# Fri3D_2020_Peripherals.net
KiCad netlist of a schematic drawn in Altium Designer
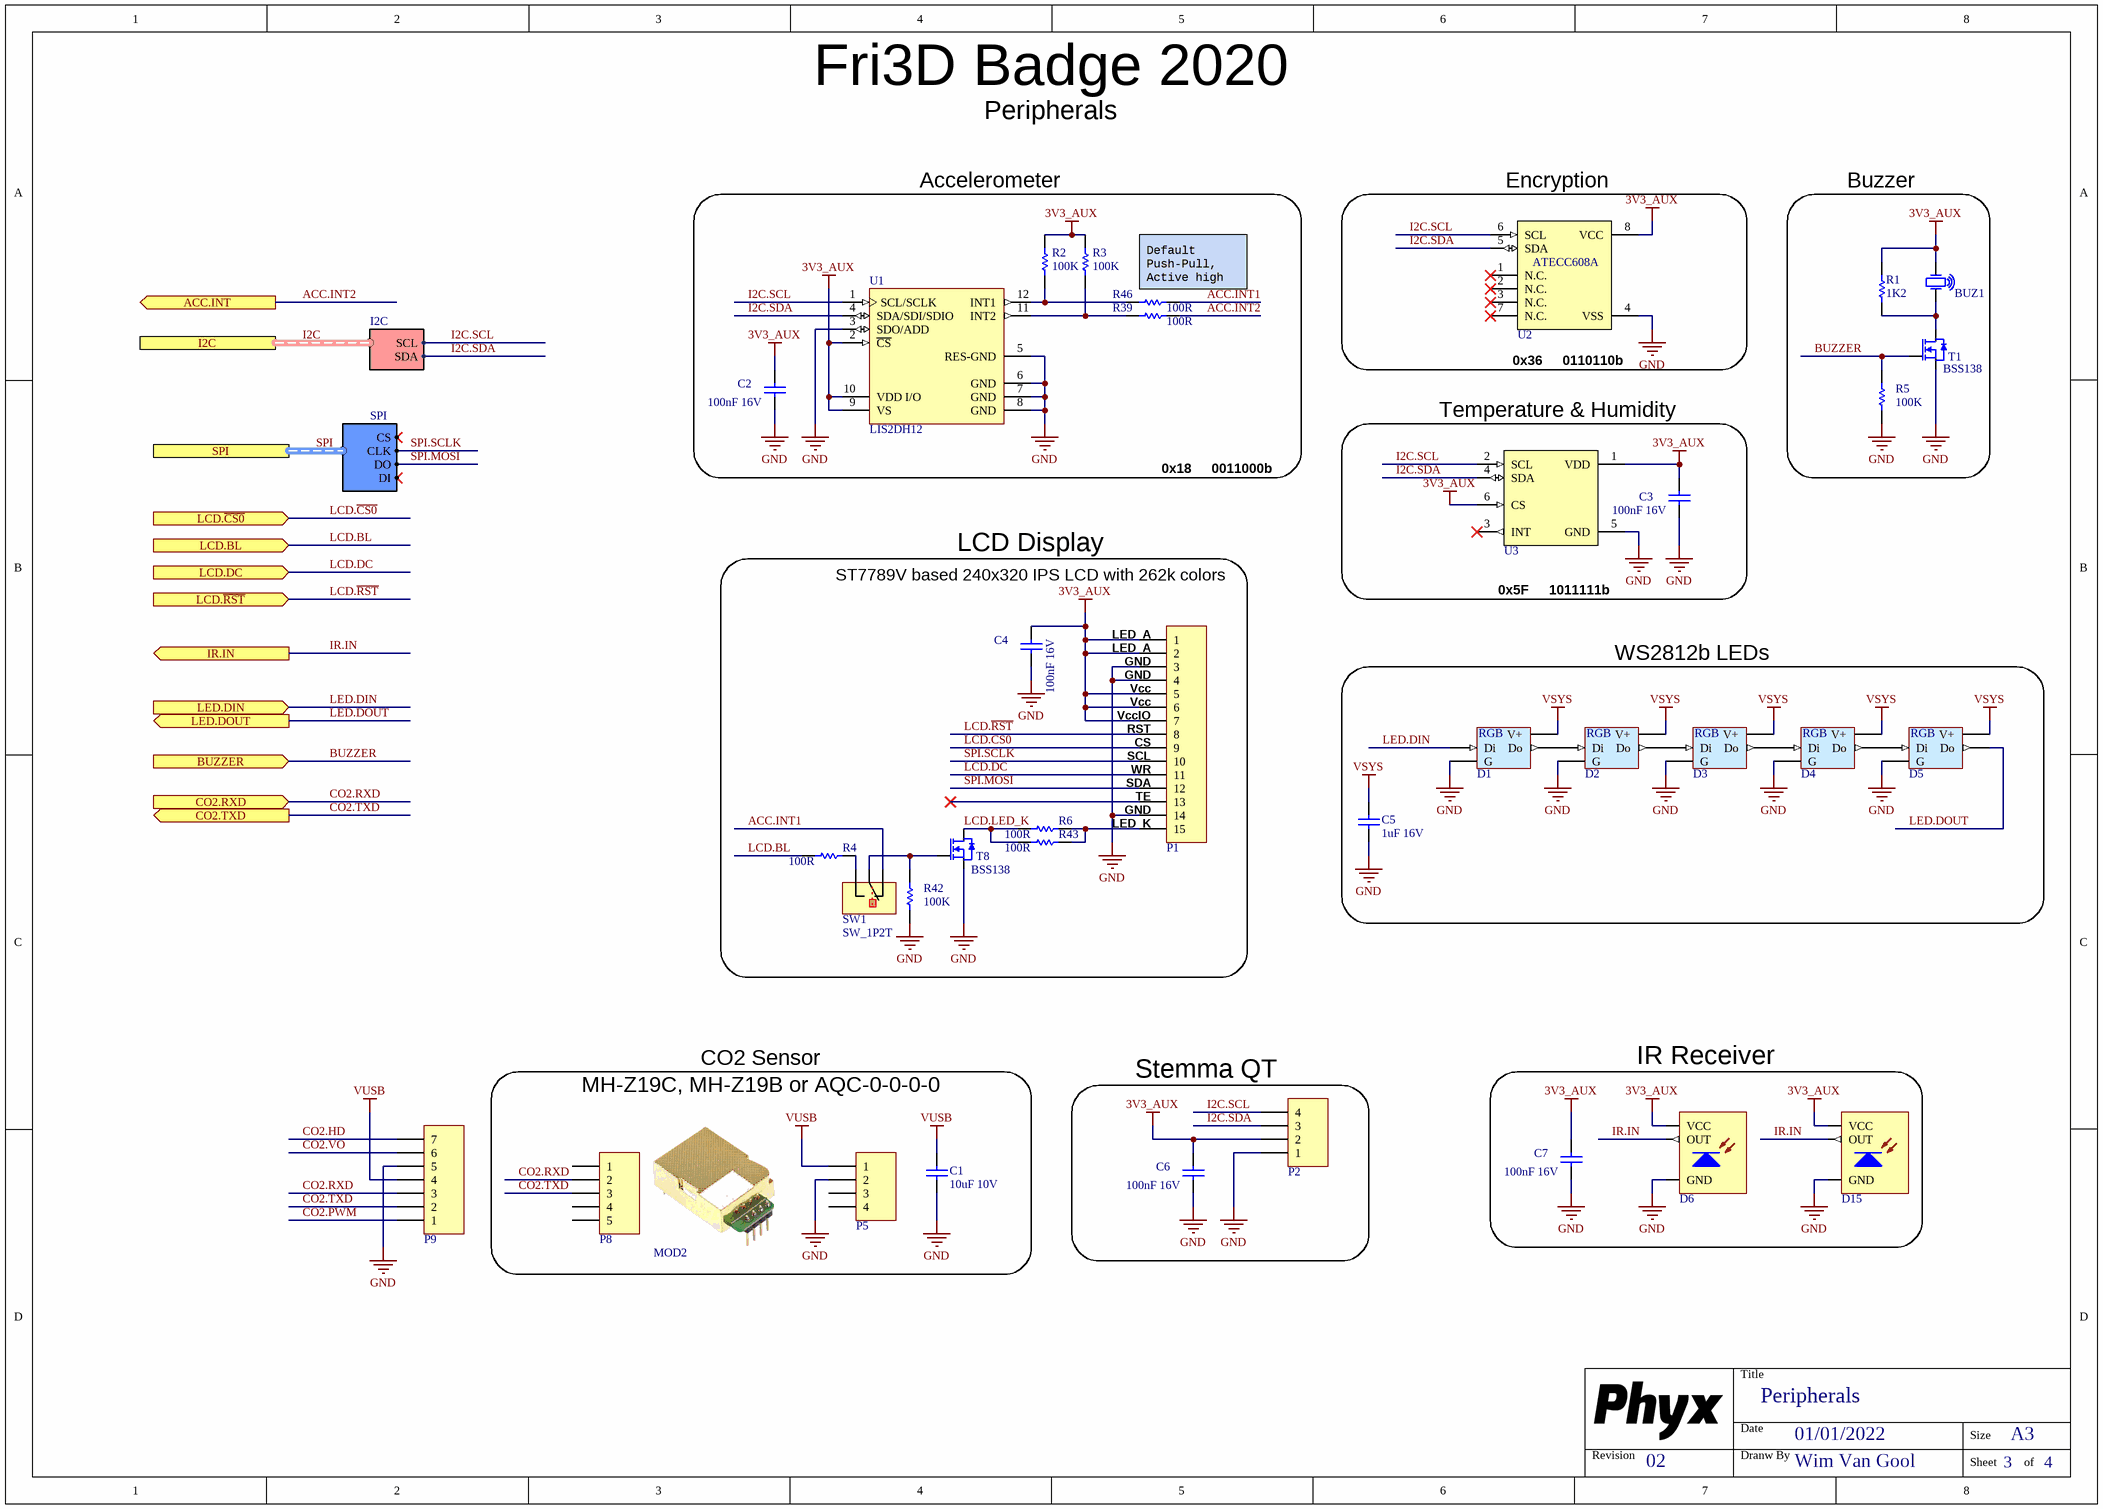
[diagram p0: Fri3D_2020_Peripherals.SchDoc]

(export (version "E")
  (design (tool "Eeschema 10.0.6"))
  (components
    (comp (ref "BUZ1")
      (value "12x12x3mm Piezo Buzzer Transducer 81dB")
      (footprint "CUI_CMT-1203-SMT")
      (description "Crystal Oscillator")
      (libsource (lib "Phyx_Components") (part "Buzzer"))
    )
    (comp (ref "C1")
      (value "10uF 10V")
      (footprint "C0805_N")
      (description "Capacitor Ceramic")
      (fields (field (name "Comment") "CAP_CERAMIC"))
      (libsource (lib "Phyx_Components") (part "CAP_CERAMIC"))
    )
    (comp (ref "C2")
      (value "100nF 16V")
      (footprint "C0603_N")
      (description "Capacitor Ceramic")
      (libsource (lib "Phyx_Components") (part "CAP_CERAMIC"))
    )
    (comp (ref "C3")
      (value "100nF 16V")
      (footprint "C0603_N")
      (description "Capacitor Ceramic")
      (libsource (lib "Phyx_Components") (part "CAP_CERAMIC"))
    )
    (comp (ref "C4")
      (value "100nF 16V")
      (footprint "C0603_N")
      (description "Capacitor Ceramic")
      (libsource (lib "Phyx_Components") (part "CAP_CERAMIC"))
    )
    (comp (ref "C5")
      (value "1uF 16V")
      (footprint "C0603_N")
      (description "Capacitor Ceramic")
      (fields (field (name "Comment") "CAP_CERAMIC"))
      (libsource (lib "Phyx_Components") (part "CAP_CERAMIC"))
    )
    (comp (ref "C6")
      (value "100nF 16V")
      (footprint "C0603_N")
      (description "Capacitor Ceramic")
      (libsource (lib "Phyx_Components") (part "CAP_CERAMIC"))
    )
    (comp (ref "C7")
      (value "100nF 16V")
      (footprint "C0603_N")
      (description "Capacitor Ceramic")
      (libsource (lib "Phyx_Components") (part "CAP_CERAMIC"))
    )
    (comp (ref "D1")
      (value "WS2812 based digital RGB LED 5050 Black package")
      (footprint "LED_5050_WS2812B_BLACK")
      (description "=Description")
      (libsource (lib "Phyx_Components") (part "LED_RGB_WS2812B_5050"))
    )
    (comp (ref "D2")
      (value "WS2812 based digital RGB LED 5050 Black package")
      (footprint "LED_5050_WS2812B_BLACK")
      (description "=Description")
      (libsource (lib "Phyx_Components") (part "LED_RGB_WS2812B_5050"))
    )
    (comp (ref "D3")
      (value "WS2812 based digital RGB LED 5050 Black package")
      (footprint "LED_5050_WS2812B_BLACK")
      (description "=Description")
      (libsource (lib "Phyx_Components") (part "LED_RGB_WS2812B_5050"))
    )
    (comp (ref "D4")
      (value "WS2812 based digital RGB LED 5050 Black package")
      (footprint "LED_5050_WS2812B_BLACK")
      (description "=Description")
      (libsource (lib "Phyx_Components") (part "LED_RGB_WS2812B_5050"))
    )
    (comp (ref "D5")
      (value "WS2812 based digital RGB LED 5050 Black package")
      (footprint "LED_5050_WS2812B_BLACK")
      (description "=Description")
      (libsource (lib "Phyx_Components") (part "LED_RGB_WS2812B_5050"))
    )
    (comp (ref "D6")
      (value "IRM-3638N3F14 Infrared Receiver 38 kHz 45° 2.7-5.5V")
      (footprint "VIS_TSOP381x_BENT")
      (description "=Description")
      (libsource (lib "Phyx_Components") (part "PHO_IR_TSOP381x"))
    )
    (comp (ref "D15")
      (value "ZIRM-5042B-42-Z2 Infrared Receiver 38 kHz 45° 2.7-5.5V 940nm")
      (footprint "CHAU_ZIRM-5042B-42-Z2")
      (description "=Description")
      (libsource (lib "Phyx_Components") (part "PHO_IR_TSOP381x"))
    )
    (comp (ref "MOD2")
      (value "MH-Z19C CO2 Sensor TH Pins")
      (footprint "WIN_MH-Z19x-PH")
      (description "CO2 MH-Z19C-PH")
      (libsource (lib "Phyx_Components") (part "WIN_MH-Z19x-PH"))
    )
    (comp (ref "P1")
      (value "Bottom contact FPC 0.3mm pitch 15 contacts")
      (footprint "FPC_AFE03-S15FMA-1H")
      (libsource (lib "Phyx_Components") (part "Header 15"))
    )
    (comp (ref "P2")
      (value "Header 1.0mm RA Shrouded 4")
      (footprint "WE_665104131822")
      (libsource (lib "Phyx_Components") (part "Header 4"))
    )
    (comp (ref "P5")
      (value "Receptacle 4 SMD Type 2")
      (footprint "WE_61000413321")
      (description "Receptacle # 2.54mm 4way Type 2")
      (libsource (lib "") (part "Header 4_1"))
    )
    (comp (ref "P8")
      (value "Receptacle 5 SMD Type 2")
      (footprint "WE_61000513321")
      (description "Receptacle # 2.54mm 5way Type 2")
      (libsource (lib "Phyx_Components") (part "Header 5"))
    )
    (comp (ref "P9")
      (value "Molex Picoblade SMD RA 532610771")
      (footprint "MLX_53261-0771")
      (description "HDR # RA SHR 1.25mm 7way Molex Picoblade")
      (libsource (lib "Phyx_Components") (part "Header 7"))
    )
    (comp (ref "R1")
      (value "1K2")
      (footprint "R0603_N")
      (fields (field (name "Comment") "RESISTOR"))
      (libsource (lib "Phyx_Components") (part "RESISTOR"))
    )
    (comp (ref "R2")
      (value "100K")
      (footprint "R0603_N")
      (fields (field (name "Comment") "RESISTOR"))
      (libsource (lib "Phyx_Components") (part "RESISTOR"))
    )
    (comp (ref "R3")
      (value "100K")
      (footprint "R0603_N")
      (fields (field (name "Comment") "RESISTOR"))
      (libsource (lib "Phyx_Components") (part "RESISTOR"))
    )
    (comp (ref "R4")
      (value "100R")
      (footprint "R0603_N")
      (fields (field (name "Comment") "RESISTOR"))
      (libsource (lib "Phyx_Components") (part "RESISTOR"))
    )
    (comp (ref "R5")
      (value "100K")
      (footprint "R0603_N")
      (fields (field (name "Comment") "RESISTOR"))
      (libsource (lib "Phyx_Components") (part "RESISTOR"))
    )
    (comp (ref "R6")
      (value "100R")
      (footprint "R0603_N")
      (fields (field (name "Comment") "RESISTOR"))
      (libsource (lib "Phyx_Components") (part "RESISTOR"))
    )
    (comp (ref "R39")
      (value "100R")
      (footprint "R0603_N")
      (fields (field (name "Comment") "RESISTOR"))
      (libsource (lib "Phyx_Components") (part "RESISTOR"))
    )
    (comp (ref "R42")
      (value "100K")
      (footprint "R0603_N")
      (fields (field (name "Comment") "RESISTOR"))
      (libsource (lib "Phyx_Components") (part "RESISTOR"))
    )
    (comp (ref "R43")
      (value "100R")
      (footprint "R0603_N")
      (fields (field (name "Comment") "RESISTOR"))
      (libsource (lib "Phyx_Components") (part "RESISTOR"))
    )
    (comp (ref "R46")
      (value "100R")
      (footprint "R0603_N")
      (fields (field (name "Comment") "RESISTOR"))
      (libsource (lib "Phyx_Components") (part "RESISTOR"))
    )
    (comp (ref "SW1")
      (value "SW_1P2T")
      (footprint "WE_450404015514")
      (libsource (lib "Phyx_Components") (part "SW_1P2T"))
    )
    (comp (ref "T1")
      (value "BSS138")
      (footprint "SOT23-3")
      (fields (field (name "Comment") "0.2A N-Ch MOSFET Vgs 3.2"))
      (libsource (lib "Phyx_Components") (part "N_MOSFET_GSD"))
    )
    (comp (ref "T8")
      (value "BSS138")
      (footprint "SOT23-3")
      (fields (field (name "Comment") "0.2A N-Ch MOSFET Vgs 3.2"))
      (libsource (lib "Phyx_Components") (part "N_MOSFET_GSD"))
    )
    (comp (ref "U1")
      (value "LIS2DH12")
      (footprint "STM_LGA12_2x2")
      (description "=Description")
      (libsource (lib "Phyx_Components") (part "STM_LIS2DH12"))
    )
    (comp (ref "U2")
      (value "Encryption Authentication with 72b SN, SHA-256, AES-128")
      (footprint "SOIC_N_8")
      (description "=Description")
      (libsource (lib "Phyx_Components") (part "ATECC608A-SSHDA"))
    )
    (comp (ref "U3")
      (value "WSEN-HIDS 2525020210001 temperature and humidity sensor Digital I2C")
      (footprint "WE_2525020210001")
      (description "=Description")
      (libsource (lib "Phyx_Components") (part "WE_2525020210001"))
    )
  )
  (nets
    (net (code "3") (name "/ACC.INT1") (class "Default")
      (node (ref "R46") (pin "2") (pinfunction "2_2") (pintype "passive"))
      (node (ref "SW1") (pin "1") (pinfunction "1_1") (pintype "passive"))
    )
    (net (code "4") (name "/ACC.INT2") (class "Default")
      (node (ref "R39") (pin "2") (pinfunction "2_2") (pintype "passive"))
    )
    (net (code "5") (name "/BUZZER") (class "Default")
      (node (ref "R5") (pin "1") (pinfunction "1_1") (pintype "passive"))
      (node (ref "T1") (pin "1") (pinfunction "G_1") (pintype "passive"))
    )
    (net (code "6") (name "/CO2.HD") (class "Default")
      (node (ref "P9") (pin "7") (pinfunction "7_7") (pintype "passive"))
    )
    (net (code "7") (name "/CO2.PWM") (class "Default")
      (node (ref "P9") (pin "1") (pinfunction "1_1") (pintype "passive"))
    )
    (net (code "8") (name "/CO2.RXD") (class "Default")
      (node (ref "P8") (pin "2") (pinfunction "2_2") (pintype "passive"))
      (node (ref "P9") (pin "3") (pinfunction "3_3") (pintype "passive"))
    )
    (net (code "9") (name "/CO2.TXD") (class "Default")
      (node (ref "P8") (pin "3") (pinfunction "3_3") (pintype "passive"))
      (node (ref "P9") (pin "2") (pinfunction "2_2") (pintype "passive"))
    )
    (net (code "10") (name "/CO2.VO") (class "Default")
      (node (ref "P9") (pin "6") (pinfunction "6_6") (pintype "passive"))
    )
    (net (code "11") (name "/I2C.SCL") (class "Default")
      (node (ref "P2") (pin "4") (pinfunction "4_4") (pintype "passive"))
      (node (ref "U1") (pin "1") (pinfunction "SCL/SCLK_1") (pintype "input"))
      (node (ref "U2") (pin "6") (pinfunction "SCL_6") (pintype "input"))
      (node (ref "U3") (pin "2") (pinfunction "SCL_2") (pintype "input"))
    )
    (net (code "12") (name "/I2C.SDA") (class "Default")
      (node (ref "P2") (pin "3") (pinfunction "3_3") (pintype "passive"))
      (node (ref "U1") (pin "4") (pinfunction "SDA/SDI/SDIO_4") (pintype "bidirectional"))
      (node (ref "U2") (pin "5") (pinfunction "SDA_5") (pintype "bidirectional"))
      (node (ref "U3") (pin "4") (pinfunction "SDA_4") (pintype "bidirectional"))
    )
    (net (code "14") (name "/IR.IN") (class "Default")
      (node (ref "D15") (pin "1") (pinfunction "OUT_1") (pintype "output"))
      (node (ref "D6") (pin "1") (pinfunction "OUT_1") (pintype "output"))
    )
    (net (code "15") (name "/LCD.BL") (class "Default")
      (node (ref "R4") (pin "2") (pinfunction "2_2") (pintype "passive"))
    )
    (net (code "16") (name "/LCD.DC") (class "Default")
      (node (ref "P1") (pin "11") (pinfunction "11_11") (pintype "passive"))
    )
    (net (code "17") (name "/LCD.LED_K") (class "Default")
      (node (ref "R43") (pin "2") (pinfunction "2_2") (pintype "passive"))
      (node (ref "R6") (pin "2") (pinfunction "2_2") (pintype "passive"))
      (node (ref "T8") (pin "3") (pinfunction "D_3") (pintype "passive"))
    )
    (net (code "18") (name "/LCD.~{CS0}") (class "Default")
      (node (ref "P1") (pin "9") (pinfunction "9_9") (pintype "passive"))
    )
    (net (code "19") (name "/LCD.~{RST}") (class "Default")
      (node (ref "P1") (pin "8") (pinfunction "8_8") (pintype "passive"))
    )
    (net (code "20") (name "/LED.DIN") (class "Default")
      (node (ref "D1") (pin "4") (pinfunction "Di_4") (pintype "input"))
    )
    (net (code "21") (name "/LED.DOUT") (class "Default")
      (node (ref "D5") (pin "2") (pinfunction "Do_2") (pintype "output"))
    )
    (net (code "22") (name "/SPI.MOSI") (class "Default")
      (node (ref "P1") (pin "12") (pinfunction "12_12") (pintype "passive"))
    )
    (net (code "23") (name "/SPI.SCLK") (class "Default")
      (node (ref "P1") (pin "10") (pinfunction "10_10") (pintype "passive"))
    )
    (net (code "25") (name "3V3_AUX") (class "Default")
      (node (ref "BUZ1") (pin "1") (pinfunction "OSC1_1") (pintype "passive"))
      (node (ref "C2") (pin "1") (pinfunction "1_1") (pintype "passive"))
      (node (ref "C3") (pin "1") (pinfunction "1_1") (pintype "passive"))
      (node (ref "C4") (pin "1") (pinfunction "1_1") (pintype "passive"))
      (node (ref "C6") (pin "1") (pinfunction "1_1") (pintype "passive"))
      (node (ref "C7") (pin "1") (pinfunction "1_1") (pintype "passive"))
      (node (ref "D15") (pin "3") (pinfunction "VCC_3") (pintype "power_in"))
      (node (ref "D6") (pin "3") (pinfunction "VCC_3") (pintype "power_in"))
      (node (ref "P1") (pin "1") (pinfunction "1_1") (pintype "passive"))
      (node (ref "P1") (pin "2") (pinfunction "2_2") (pintype "passive"))
      (node (ref "P1") (pin "5") (pinfunction "5_5") (pintype "passive"))
      (node (ref "P1") (pin "6") (pinfunction "6_6") (pintype "passive"))
      (node (ref "P1") (pin "7") (pinfunction "7_7") (pintype "passive"))
      (node (ref "P2") (pin "2") (pinfunction "2_2") (pintype "passive"))
      (node (ref "R1") (pin "1") (pinfunction "1_1") (pintype "passive"))
      (node (ref "R2") (pin "1") (pinfunction "1_1") (pintype "passive"))
      (node (ref "R3") (pin "1") (pinfunction "1_1") (pintype "passive"))
      (node (ref "U1") (pin "10") (pinfunction "VDD_I/O_10") (pintype "power_in"))
      (node (ref "U1") (pin "2") (pinfunction "~{CS}_2") (pintype "input"))
      (node (ref "U1") (pin "9") (pinfunction "VS_9") (pintype "power_in"))
      (node (ref "U2") (pin "8") (pinfunction "VCC_8") (pintype "power_in"))
      (node (ref "U3") (pin "1") (pinfunction "VDD_1") (pintype "power_in"))
      (node (ref "U3") (pin "6") (pinfunction "CS_6") (pintype "input"))
    )
    (net (code "26") (name "GND") (class "Default")
      (node (ref "C1") (pin "2") (pinfunction "2_2") (pintype "passive"))
      (node (ref "C2") (pin "2") (pinfunction "2_2") (pintype "passive"))
      (node (ref "C3") (pin "2") (pinfunction "2_2") (pintype "passive"))
      (node (ref "C4") (pin "2") (pinfunction "2_2") (pintype "passive"))
      (node (ref "C5") (pin "2") (pinfunction "2_2") (pintype "passive"))
      (node (ref "C6") (pin "2") (pinfunction "2_2") (pintype "passive"))
      (node (ref "C7") (pin "2") (pinfunction "2_2") (pintype "passive"))
      (node (ref "D1") (pin "3") (pinfunction "G_3") (pintype "power_in"))
      (node (ref "D15") (pin "2") (pinfunction "GND_2") (pintype "power_in"))
      (node (ref "D2") (pin "3") (pinfunction "G_3") (pintype "power_in"))
      (node (ref "D3") (pin "3") (pinfunction "G_3") (pintype "power_in"))
      (node (ref "D4") (pin "3") (pinfunction "G_3") (pintype "power_in"))
      (node (ref "D5") (pin "3") (pinfunction "G_3") (pintype "power_in"))
      (node (ref "D6") (pin "2") (pinfunction "GND_2") (pintype "power_in"))
      (node (ref "P1") (pin "14") (pinfunction "14_14") (pintype "passive"))
      (node (ref "P1") (pin "3") (pinfunction "3_3") (pintype "passive"))
      (node (ref "P1") (pin "4") (pinfunction "4_4") (pintype "passive"))
      (node (ref "P2") (pin "1") (pinfunction "1_1") (pintype "passive"))
      (node (ref "P5") (pin "2") (pinfunction "2_2") (pintype "passive"))
      (node (ref "P9") (pin "5") (pinfunction "5_5") (pintype "passive"))
      (node (ref "R42") (pin "2") (pinfunction "2_2") (pintype "passive"))
      (node (ref "R5") (pin "2") (pinfunction "2_2") (pintype "passive"))
      (node (ref "T1") (pin "2") (pinfunction "S_2") (pintype "passive"))
      (node (ref "T8") (pin "2") (pinfunction "S_2") (pintype "passive"))
      (node (ref "U1") (pin "3") (pinfunction "SDO/ADD_3") (pintype "bidirectional"))
      (node (ref "U1") (pin "5") (pinfunction "RES-GND_5") (pintype "passive"))
      (node (ref "U1") (pin "6") (pinfunction "GND_6") (pintype "power_in"))
      (node (ref "U1") (pin "7") (pinfunction "GND_7") (pintype "power_in"))
      (node (ref "U1") (pin "8") (pinfunction "GND_8") (pintype "power_in"))
      (node (ref "U2") (pin "4") (pinfunction "VSS_4") (pintype "power_in"))
      (node (ref "U3") (pin "5") (pinfunction "GND_5") (pintype "power_in"))
    )
    (net (code "27") (name "Net-(BUZ1-OSC2)") (class "Default")
      (node (ref "BUZ1") (pin "2") (pinfunction "OSC2_2") (pintype "passive"))
      (node (ref "R1") (pin "2") (pinfunction "2_2") (pintype "passive"))
      (node (ref "T1") (pin "3") (pinfunction "D_3") (pintype "passive"))
    )
    (net (code "28") (name "Net-(D1-Do)") (class "Default")
      (node (ref "D1") (pin "2") (pinfunction "Do_2") (pintype "output"))
      (node (ref "D2") (pin "4") (pinfunction "Di_4") (pintype "input"))
    )
    (net (code "29") (name "Net-(D2-Do)") (class "Default")
      (node (ref "D2") (pin "2") (pinfunction "Do_2") (pintype "output"))
      (node (ref "D3") (pin "4") (pinfunction "Di_4") (pintype "input"))
    )
    (net (code "30") (name "Net-(D3-Do)") (class "Default")
      (node (ref "D3") (pin "2") (pinfunction "Do_2") (pintype "output"))
      (node (ref "D4") (pin "4") (pinfunction "Di_4") (pintype "input"))
    )
    (net (code "31") (name "Net-(D4-Do)") (class "Default")
      (node (ref "D4") (pin "2") (pinfunction "Do_2") (pintype "output"))
      (node (ref "D5") (pin "4") (pinfunction "Di_4") (pintype "input"))
    )
    (net (code "32") (name "Net-(P1-Pad15)") (class "Default")
      (node (ref "P1") (pin "15") (pinfunction "15_15") (pintype "passive"))
      (node (ref "R43") (pin "1") (pinfunction "1_1") (pintype "passive"))
      (node (ref "R6") (pin "1") (pinfunction "1_1") (pintype "passive"))
    )
    (net (code "33") (name "Net-(R4-Pad1)") (class "Default")
      (node (ref "R4") (pin "1") (pinfunction "1_1") (pintype "passive"))
      (node (ref "SW1") (pin "3") (pinfunction "3_3") (pintype "passive"))
    )
    (net (code "34") (name "Net-(T8-G)") (class "Default")
      (node (ref "R42") (pin "1") (pinfunction "1_1") (pintype "passive"))
      (node (ref "SW1") (pin "2") (pinfunction "2_2") (pintype "passive"))
      (node (ref "T8") (pin "1") (pinfunction "G_1") (pintype "passive"))
    )
    (net (code "35") (name "Net-(U1-INT1)") (class "Default")
      (node (ref "R2") (pin "2") (pinfunction "2_2") (pintype "passive"))
      (node (ref "R46") (pin "1") (pinfunction "1_1") (pintype "passive"))
      (node (ref "U1") (pin "12") (pinfunction "INT1_12") (pintype "output"))
    )
    (net (code "36") (name "Net-(U1-INT2)") (class "Default")
      (node (ref "R3") (pin "2") (pinfunction "2_2") (pintype "passive"))
      (node (ref "R39") (pin "1") (pinfunction "1_1") (pintype "passive"))
      (node (ref "U1") (pin "11") (pinfunction "INT2_11") (pintype "output"))
    )
    (net (code "37") (name "VSYS") (class "Default")
      (node (ref "C5") (pin "1") (pinfunction "1_1") (pintype "passive"))
      (node (ref "D1") (pin "1") (pinfunction "V+_1") (pintype "power_in"))
      (node (ref "D2") (pin "1") (pinfunction "V+_1") (pintype "power_in"))
      (node (ref "D3") (pin "1") (pinfunction "V+_1") (pintype "power_in"))
      (node (ref "D4") (pin "1") (pinfunction "V+_1") (pintype "power_in"))
      (node (ref "D5") (pin "1") (pinfunction "V+_1") (pintype "power_in"))
    )
    (net (code "38") (name "VUSB") (class "Default")
      (node (ref "C1") (pin "1") (pinfunction "1_1") (pintype "passive"))
      (node (ref "P5") (pin "1") (pinfunction "1_1") (pintype "passive"))
      (node (ref "P9") (pin "4") (pinfunction "4_4") (pintype "passive"))
    )
    (net (code "39") (name "unconnected-(P1-Pad13)") (class "Default")
      (node (ref "P1") (pin "13") (pinfunction "13_13") (pintype "passive+no_connect"))
    )
    (net (code "40") (name "unconnected-(P5-Pad3)") (class "Default")
      (node (ref "P5") (pin "3") (pinfunction "3_3") (pintype "passive"))
    )
    (net (code "41") (name "unconnected-(P5-Pad4)") (class "Default")
      (node (ref "P5") (pin "4") (pinfunction "4_4") (pintype "passive"))
    )
    (net (code "42") (name "unconnected-(P8-Pad1)") (class "Default")
      (node (ref "P8") (pin "1") (pinfunction "1_1") (pintype "passive"))
    )
    (net (code "43") (name "unconnected-(P8-Pad4)") (class "Default")
      (node (ref "P8") (pin "4") (pinfunction "4_4") (pintype "passive"))
    )
    (net (code "44") (name "unconnected-(P8-Pad5)") (class "Default")
      (node (ref "P8") (pin "5") (pinfunction "5_5") (pintype "passive"))
    )
    (net (code "45") (name "unconnected-(U2-N.C.-Pad1)") (class "Default")
      (node (ref "U2") (pin "1") (pinfunction "N.C._1") (pintype "passive+no_connect"))
    )
    (net (code "46") (name "unconnected-(U2-N.C.-Pad2)") (class "Default")
      (node (ref "U2") (pin "2") (pinfunction "N.C._2") (pintype "passive+no_connect"))
    )
    (net (code "47") (name "unconnected-(U2-N.C.-Pad3)") (class "Default")
      (node (ref "U2") (pin "3") (pinfunction "N.C._3") (pintype "passive+no_connect"))
    )
    (net (code "48") (name "unconnected-(U2-N.C.-Pad7)") (class "Default")
      (node (ref "U2") (pin "7") (pinfunction "N.C._7") (pintype "passive+no_connect"))
    )
    (net (code "49") (name "unconnected-(U3-INT-Pad3)") (class "Default")
      (node (ref "U3") (pin "3") (pinfunction "INT_3") (pintype "output+no_connect"))
    )
  )
)
